# design.net
KiCad netlist of a schematic drawn in Altium Designer
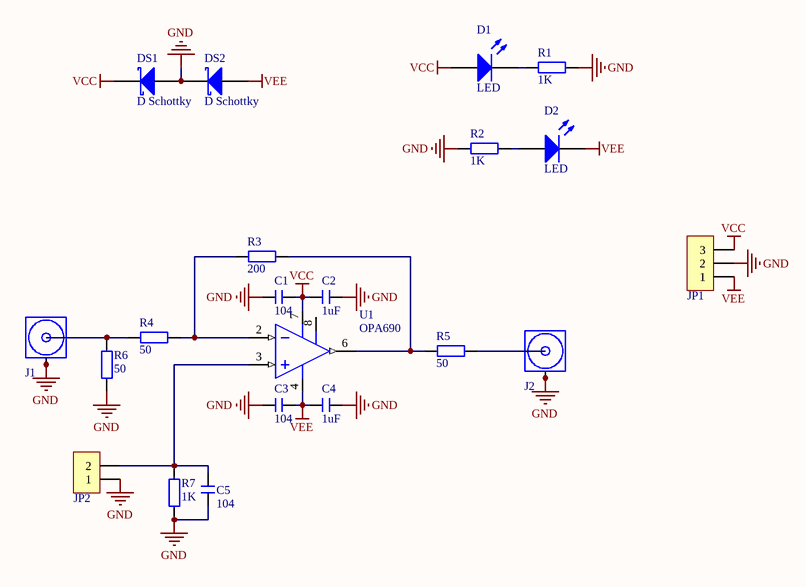
[diagram p0: 调偏电路.SchDoc]

(export (version "E")
  (design (tool "Eeschema 10.0.6"))
  (components
    (comp (ref "C1")
      (value "104")
      (footprint "C 0603")
      (description "无极性贴片电容")
      (fields (field (name "版权归属") "源创客"))
      (libsource (lib "电阻-电容-电感") (part "C"))
    )
    (comp (ref "C2")
      (value "1uF")
      (footprint "C 0603")
      (description "无极性贴片电容")
      (fields (field (name "版权归属") "源创客"))
      (libsource (lib "电阻-电容-电感") (part "C"))
    )
    (comp (ref "C3")
      (value "104")
      (footprint "C 0603")
      (description "无极性贴片电容")
      (fields (field (name "版权归属") "源创客"))
      (libsource (lib "电阻-电容-电感") (part "C"))
    )
    (comp (ref "C4")
      (value "1uF")
      (footprint "C 0603")
      (description "无极性贴片电容")
      (fields (field (name "版权归属") "源创客"))
      (libsource (lib "电阻-电容-电感") (part "C"))
    )
    (comp (ref "C5")
      (value "104")
      (footprint "C 0603")
      (description "无极性贴片电容")
      (fields (field (name "版权归属") "源创客"))
      (libsource (lib "电阻-电容-电感") (part "C"))
    )
    (comp (ref "D1")
      (value "LED")
      (footprint "LED_0805")
      (description "发光二极管")
      (fields (field (name "PUBLISHER") "Altium Limited"))
      (libsource (lib "LIB") (part "LED"))
    )
    (comp (ref "D2")
      (value "LED")
      (footprint "LED_0805")
      (description "发光二极管")
      (fields (field (name "PUBLISHER") "Altium Limited"))
      (libsource (lib "LIB") (part "LED"))
    )
    (comp (ref "DS1")
      (value "D Schottky")
      (footprint "DIODE-SMA")
      (description "Schottky Diode")
      (fields (field (name "PUBLISHER") "Altium Limited"))
      (libsource (lib "LIB") (part "D Schottky"))
    )
    (comp (ref "DS2")
      (value "D Schottky")
      (footprint "DIODE-SMA")
      (description "Schottky Diode")
      (fields (field (name "PUBLISHER") "Altium Limited"))
      (libsource (lib "LIB") (part "D Schottky"))
    )
    (comp (ref "J1") (value "COAX") (footprint "MCX5.08-5-H") (libsource (lib "LIB") (part "COAX")))
    (comp (ref "J2") (value "COAX") (footprint "MCX5.08-5-H") (libsource (lib "LIB") (part "COAX")))
    (comp (ref "JP1")
      (value "HDR-1X3")
      (footprint "XH2.54-3P_H")
      (description "3P接插件")
      (fields (field (name "版权归属") "源创客"))
      (libsource (lib "接插件") (part "Header 3"))
    )
    (comp (ref "JP2")
      (value "HDR-1X2")
      (footprint "HDR-1X2")
      (description "2P接插件")
      (fields (field (name "版权归属") "源创客"))
      (libsource (lib "接插件") (part "Header 2"))
    )
    (comp (ref "R1")
      (value "1K")
      (footprint "R 0805")
      (description "贴片电阻")
      (fields (field (name "版权归属") "源创客"))
      (libsource (lib "电阻-电容-电感") (part "R"))
    )
    (comp (ref "R2")
      (value "1K")
      (footprint "R 0805")
      (description "贴片电阻")
      (fields (field (name "版权归属") "源创客"))
      (libsource (lib "电阻-电容-电感") (part "R"))
    )
    (comp (ref "R3")
      (value "200")
      (footprint "R 0603")
      (description "贴片电阻")
      (fields (field (name "版权归属") "源创客"))
      (libsource (lib "电阻-电容-电感") (part "R"))
    )
    (comp (ref "R4")
      (value "50")
      (footprint "R 0603")
      (description "贴片电阻")
      (fields (field (name "版权归属") "源创客"))
      (libsource (lib "电阻-电容-电感") (part "R"))
    )
    (comp (ref "R5")
      (value "50")
      (footprint "R 0603")
      (description "贴片电阻")
      (fields (field (name "版权归属") "源创客"))
      (libsource (lib "电阻-电容-电感") (part "R"))
    )
    (comp (ref "R6")
      (value "50")
      (footprint "R 0603")
      (description "贴片电阻")
      (fields (field (name "版权归属") "源创客"))
      (libsource (lib "电阻-电容-电感") (part "R"))
    )
    (comp (ref "R7")
      (value "1K")
      (footprint "R 0603")
      (description "贴片电阻")
      (fields (field (name "版权归属") "源创客"))
      (libsource (lib "电阻-电容-电感") (part "R"))
    )
    (comp (ref "U1")
      (value "OPA690")
      (footprint "LIB:SOIC8_N")
      (description "具有禁用功能的宽带电压反馈运算放大器")
      (libsource (lib "LIB") (part "OPA690ID"))
    )
  )
  (nets
    (net (code "1") (name "GND") (class "Default")
      (node (ref "C1") (pin "1") (pinfunction "1_1") (pintype "passive"))
      (node (ref "C2") (pin "2") (pinfunction "2_2") (pintype "passive"))
      (node (ref "C3") (pin "1") (pinfunction "1_1") (pintype "passive"))
      (node (ref "C4") (pin "2") (pinfunction "2_2") (pintype "passive"))
      (node (ref "C5") (pin "1") (pinfunction "1_1") (pintype "passive"))
      (node (ref "DS1") (pin "1") (pinfunction "1_1") (pintype "passive"))
      (node (ref "DS2") (pin "2") (pinfunction "2_2") (pintype "passive"))
      (node (ref "J1") (pin "2") (pinfunction "GND_2") (pintype "passive"))
      (node (ref "J1") (pin "3") (pinfunction "GND_3") (pintype "passive"))
      (node (ref "J1") (pin "4") (pinfunction "GND_4") (pintype "passive"))
      (node (ref "J1") (pin "5") (pinfunction "GND_5") (pintype "passive"))
      (node (ref "J2") (pin "2") (pinfunction "GND_2") (pintype "passive"))
      (node (ref "J2") (pin "3") (pinfunction "GND_3") (pintype "passive"))
      (node (ref "J2") (pin "4") (pinfunction "GND_4") (pintype "passive"))
      (node (ref "J2") (pin "5") (pinfunction "GND_5") (pintype "passive"))
      (node (ref "JP1") (pin "2") (pinfunction "2_2") (pintype "passive"))
      (node (ref "JP2") (pin "1") (pinfunction "1_1") (pintype "passive"))
      (node (ref "R1") (pin "2") (pinfunction "2_2") (pintype "passive"))
      (node (ref "R2") (pin "1") (pinfunction "1_1") (pintype "passive"))
      (node (ref "R6") (pin "1") (pinfunction "1_1") (pintype "passive"))
      (node (ref "R7") (pin "1") (pinfunction "1_1") (pintype "passive"))
    )
    (net (code "2") (name "Net-(D1-K)") (class "Default")
      (node (ref "D1") (pin "2") (pinfunction "K_2") (pintype "passive"))
      (node (ref "R1") (pin "1") (pinfunction "1_1") (pintype "passive"))
    )
    (net (code "3") (name "Net-(D2-A)") (class "Default")
      (node (ref "D2") (pin "1") (pinfunction "A_1") (pintype "passive"))
      (node (ref "R2") (pin "2") (pinfunction "2_2") (pintype "passive"))
    )
    (net (code "4") (name "Net-(J1-Signal)") (class "Default")
      (node (ref "J1") (pin "1") (pinfunction "Signal_1") (pintype "passive"))
      (node (ref "R4") (pin "1") (pinfunction "1_1") (pintype "passive"))
      (node (ref "R6") (pin "2") (pinfunction "2_2") (pintype "passive"))
    )
    (net (code "5") (name "Net-(J2-Signal)") (class "Default")
      (node (ref "J2") (pin "1") (pinfunction "Signal_1") (pintype "passive"))
      (node (ref "R5") (pin "2") (pinfunction "2_2") (pintype "passive"))
    )
    (net (code "6") (name "Net-(U1-IN+)") (class "Default")
      (node (ref "C5") (pin "2") (pinfunction "2_2") (pintype "passive"))
      (node (ref "JP2") (pin "2") (pinfunction "2_2") (pintype "passive"))
      (node (ref "R7") (pin "2") (pinfunction "2_2") (pintype "passive"))
      (node (ref "U1") (pin "3") (pinfunction "IN+_3") (pintype "input"))
    )
    (net (code "7") (name "Net-(U1-IN-)") (class "Default")
      (node (ref "R3") (pin "1") (pinfunction "1_1") (pintype "passive"))
      (node (ref "R4") (pin "2") (pinfunction "2_2") (pintype "passive"))
      (node (ref "U1") (pin "2") (pinfunction "IN-_2") (pintype "input"))
    )
    (net (code "8") (name "Net-(U1-OUT)") (class "Default")
      (node (ref "R3") (pin "2") (pinfunction "2_2") (pintype "passive"))
      (node (ref "R5") (pin "1") (pinfunction "1_1") (pintype "passive"))
      (node (ref "U1") (pin "6") (pinfunction "OUT_6") (pintype "output"))
    )
    (net (code "9") (name "VCC") (class "Default")
      (node (ref "C1") (pin "2") (pinfunction "2_2") (pintype "passive"))
      (node (ref "C2") (pin "1") (pinfunction "1_1") (pintype "passive"))
      (node (ref "D1") (pin "1") (pinfunction "A_1") (pintype "passive"))
      (node (ref "DS1") (pin "2") (pinfunction "2_2") (pintype "passive"))
      (node (ref "JP1") (pin "3") (pinfunction "3_3") (pintype "passive"))
      (node (ref "U1") (pin "7") (pinfunction "V+_7") (pintype "power_in"))
    )
    (net (code "10") (name "VEE") (class "Default")
      (node (ref "C3") (pin "2") (pinfunction "2_2") (pintype "passive"))
      (node (ref "C4") (pin "1") (pinfunction "1_1") (pintype "passive"))
      (node (ref "D2") (pin "2") (pinfunction "K_2") (pintype "passive"))
      (node (ref "DS2") (pin "1") (pinfunction "1_1") (pintype "passive"))
      (node (ref "JP1") (pin "1") (pinfunction "1_1") (pintype "passive"))
      (node (ref "U1") (pin "4") (pinfunction "V-_4") (pintype "power_in"))
    )
    (net (code "11") (name "unconnected-(U1-DIS-Pad8)") (class "Default")
      (node (ref "U1") (pin "8") (pinfunction "DIS_8") (pintype "passive"))
    )
  )
)
